# Dianome.net
KiCad netlist of a schematic drawn in EAGLE
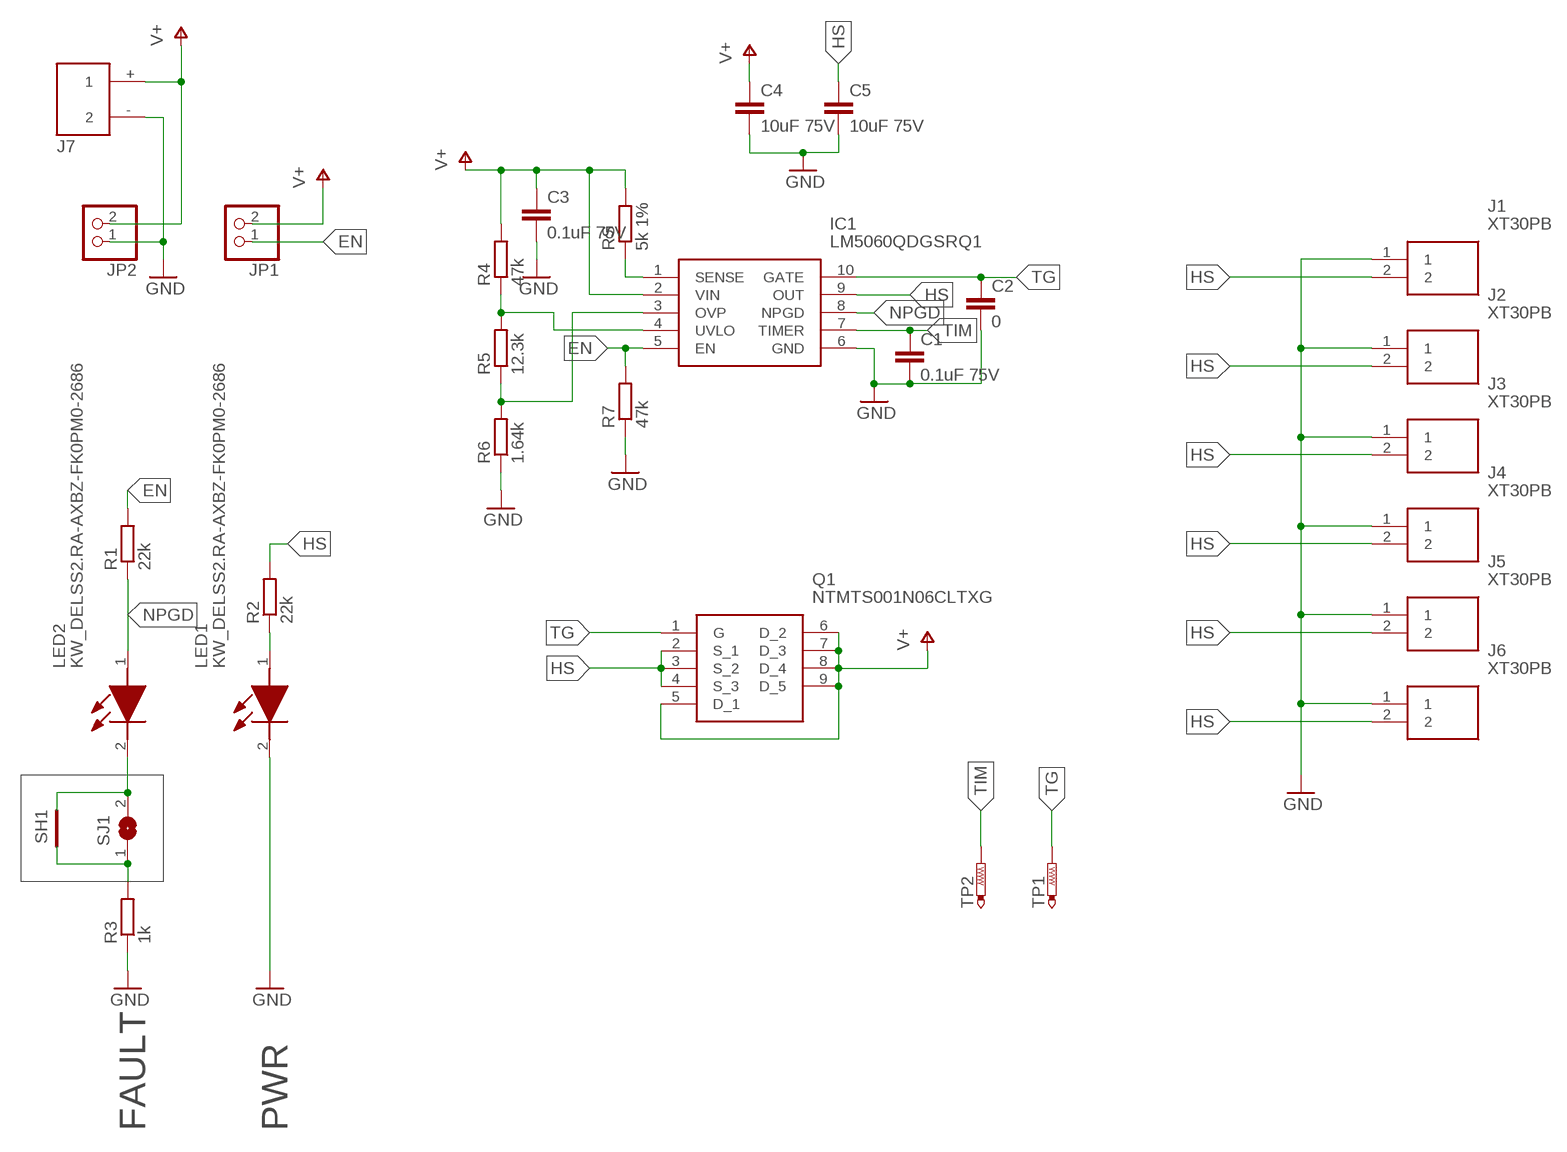
[diagram p0: schematic, sheet 1]

(export (version "E")
  (design (tool "Eeschema 10.0.6"))
  (components
    (comp (ref "C1")
      (value "0.1uF 75V")
      (footprint "eagle-import:C0603K")
      (libsource (lib "eagle-import") (part "C-EUC0603K"))
    )
    (comp (ref "C2")
      (value "0")
      (footprint "eagle-import:C0603K")
      (libsource (lib "eagle-import") (part "C-EUC0603K"))
    )
    (comp (ref "C3")
      (value "0.1uF 75V")
      (footprint "eagle-import:C0603K")
      (libsource (lib "eagle-import") (part "C-EUC0603K"))
    )
    (comp (ref "C4")
      (value "10uF 75V")
      (footprint "eagle-import:C1210")
      (libsource (lib "eagle-import") (part "C-EUC1210"))
    )
    (comp (ref "C5")
      (value "10uF 75V")
      (footprint "eagle-import:C1210")
      (libsource (lib "eagle-import") (part "C-EUC1210"))
    )
    (comp (ref "IC1")
      (value "LM5060QDGSRQ1")
      (footprint "eagle-import:SOP50P490X110-10N")
      (fields (field (name "MOUSER_PART_NUMBER") "595-LM5060QDGSRQ1"))
      (libsource (lib "eagle-import") (part "LM5060QDGSRQ1"))
    )
    (comp (ref "J1")
      (value "XT30PB")
      (footprint "eagle-import:XT30PB")
      (libsource (lib "eagle-import") (part "XT30PB"))
    )
    (comp (ref "J2")
      (value "XT30PB")
      (footprint "eagle-import:XT30PB")
      (libsource (lib "eagle-import") (part "XT30PB"))
    )
    (comp (ref "J3")
      (value "XT30PB")
      (footprint "eagle-import:XT30PB")
      (libsource (lib "eagle-import") (part "XT30PB"))
    )
    (comp (ref "J4")
      (value "XT30PB")
      (footprint "eagle-import:XT30PB")
      (libsource (lib "eagle-import") (part "XT30PB"))
    )
    (comp (ref "J5")
      (value "XT30PB")
      (footprint "eagle-import:XT30PB")
      (libsource (lib "eagle-import") (part "XT30PB"))
    )
    (comp (ref "J6")
      (value "XT30PB")
      (footprint "eagle-import:XT30PB")
      (libsource (lib "eagle-import") (part "XT30PB"))
    )
    (comp (ref "J7")
      (value "XT60_FEMALE")
      (footprint "eagle-import:XT60_FEMALE")
      (libsource (lib "eagle-import") (part "XT60_FEMALE"))
    )
    (comp (ref "JP1")
      (value "PINHD-1X02_2.54-S")
      (footprint "eagle-import:1X02-S")
      (libsource (lib "eagle-import") (part "PINHD-1X02_2.54-S"))
    )
    (comp (ref "JP2")
      (value "PINHD-1X02_2.54-S")
      (footprint "eagle-import:1X02-S")
      (libsource (lib "eagle-import") (part "PINHD-1X02_2.54-S"))
    )
    (comp (ref "LED1")
      (value "KW_DELSS2.RA-AXBZ-FK0PM0-2686")
      (footprint "eagle-import:KWDELSS2RAAXBZFK0PM02686")
      (fields
        (field (name "ARROW_PART_NUMBER") "KW DELSS2.RA-AXBZ-FK0PM0-2686")
        (field (name "MOUSER_PART_NUMBER") "720-KWDELSS2RAA6162")
      )
      (libsource (lib "eagle-import") (part "KW_DELSS2.RA-AXBZ-FK0PM0-2686"))
    )
    (comp (ref "LED2")
      (value "KW_DELSS2.RA-AXBZ-FK0PM0-2686")
      (footprint "eagle-import:KWDELSS2RAAXBZFK0PM02686")
      (fields
        (field (name "ARROW_PART_NUMBER") "KW DELSS2.RA-AXBZ-FK0PM0-2686")
        (field (name "MOUSER_PART_NUMBER") "720-KWDELSS2RAA6162")
      )
      (libsource (lib "eagle-import") (part "KW_DELSS2.RA-AXBZ-FK0PM0-2686"))
    )
    (comp (ref "Q1")
      (value "NTMTS001N06CLTXG")
      (footprint "eagle-import:NTMTS001N06CLTXG")
      (fields (field (name "MOUSER_PART_NUMBER") "863-NTMTS001N06CLTXG"))
      (libsource (lib "eagle-import") (part "NTMTS001N06CLTXG"))
    )
    (comp (ref "R1")
      (value "22k")
      (footprint "eagle-import:R0603")
      (libsource (lib "eagle-import") (part "R-EU_R0603"))
    )
    (comp (ref "R2")
      (value "22k")
      (footprint "eagle-import:R0603")
      (libsource (lib "eagle-import") (part "R-EU_R0603"))
    )
    (comp (ref "R3")
      (value "1k")
      (footprint "eagle-import:R0603")
      (libsource (lib "eagle-import") (part "R-EU_R0603"))
    )
    (comp (ref "R4")
      (value "47k")
      (footprint "eagle-import:R0603")
      (libsource (lib "eagle-import") (part "R-EU_R0603"))
    )
    (comp (ref "R5")
      (value "12.3k")
      (footprint "eagle-import:R0603")
      (libsource (lib "eagle-import") (part "R-EU_R0603"))
    )
    (comp (ref "R6")
      (value "1.64k")
      (footprint "eagle-import:R0603")
      (libsource (lib "eagle-import") (part "R-EU_R0603"))
    )
    (comp (ref "R7")
      (value "47k")
      (footprint "eagle-import:R0603")
      (libsource (lib "eagle-import") (part "R-EU_R0603"))
    )
    (comp (ref "RS")
      (value "5k 1%")
      (footprint "eagle-import:R0603")
      (libsource (lib "eagle-import") (part "R-EU_R0603"))
    )
    (comp (ref "SH1")
      (value "SHORTT5")
      (footprint "eagle-import:SHORT_TOP-50")
      (libsource (lib "eagle-import") (part "SHORTT5"))
    )
    (comp (ref "SJ1") (value "SJ") (footprint "eagle-import:SJ") (libsource (lib "eagle-import") (part "SJ")))
    (comp (ref "TP1")
      (value "PTR1PAD1-13")
      (footprint "eagle-import:P1-13")
      (libsource (lib "eagle-import") (part "PTR1PAD1-13"))
    )
    (comp (ref "TP2")
      (value "PTR1PAD1-13")
      (footprint "eagle-import:P1-13")
      (libsource (lib "eagle-import") (part "PTR1PAD1-13"))
    )
  )
  (nets
    (net (code "1") (name "EN") (class "Default")
      (node (ref "IC1") (pin "5") (pinfunction "EN_5") (pintype "bidirectional"))
      (node (ref "JP1") (pin "1") (pinfunction "1_1") (pintype "passive"))
      (node (ref "R1") (pin "2") (pinfunction "2_2") (pintype "passive"))
      (node (ref "R7") (pin "2") (pinfunction "2_2") (pintype "passive"))
    )
    (net (code "2") (name "GND") (class "Default")
      (node (ref "C1") (pin "2") (pinfunction "2_2") (pintype "passive"))
      (node (ref "C2") (pin "2") (pinfunction "2_2") (pintype "passive"))
      (node (ref "C3") (pin "2") (pinfunction "2_2") (pintype "passive"))
      (node (ref "C4") (pin "2") (pinfunction "2_2") (pintype "passive"))
      (node (ref "C5") (pin "2") (pinfunction "2_2") (pintype "passive"))
      (node (ref "IC1") (pin "6") (pinfunction "GND_6") (pintype "bidirectional"))
      (node (ref "J1") (pin "1") (pinfunction "1_1") (pintype "bidirectional"))
      (node (ref "J2") (pin "1") (pinfunction "1_1") (pintype "bidirectional"))
      (node (ref "J3") (pin "1") (pinfunction "1_1") (pintype "bidirectional"))
      (node (ref "J4") (pin "1") (pinfunction "1_1") (pintype "bidirectional"))
      (node (ref "J5") (pin "1") (pinfunction "1_1") (pintype "bidirectional"))
      (node (ref "J6") (pin "1") (pinfunction "1_1") (pintype "bidirectional"))
      (node (ref "J7") (pin "-") (pinfunction "2_-") (pintype "bidirectional"))
      (node (ref "JP2") (pin "1") (pinfunction "1_1") (pintype "passive"))
      (node (ref "LED1") (pin "2") (pinfunction "K_2") (pintype "bidirectional"))
      (node (ref "R3") (pin "1") (pinfunction "1_1") (pintype "passive"))
      (node (ref "R6") (pin "1") (pinfunction "1_1") (pintype "passive"))
      (node (ref "R7") (pin "1") (pinfunction "1_1") (pintype "passive"))
    )
    (net (code "3") (name "HS") (class "Default")
      (node (ref "C5") (pin "1") (pinfunction "1_1") (pintype "passive"))
      (node (ref "IC1") (pin "9") (pinfunction "OUT_9") (pintype "bidirectional"))
      (node (ref "J1") (pin "2") (pinfunction "2_2") (pintype "bidirectional"))
      (node (ref "J2") (pin "2") (pinfunction "2_2") (pintype "bidirectional"))
      (node (ref "J3") (pin "2") (pinfunction "2_2") (pintype "bidirectional"))
      (node (ref "J4") (pin "2") (pinfunction "2_2") (pintype "bidirectional"))
      (node (ref "J5") (pin "2") (pinfunction "2_2") (pintype "bidirectional"))
      (node (ref "J6") (pin "2") (pinfunction "2_2") (pintype "bidirectional"))
      (node (ref "Q1") (pin "2") (pinfunction "S_1_2") (pintype "bidirectional"))
      (node (ref "Q1") (pin "3") (pinfunction "S_2_3") (pintype "bidirectional"))
      (node (ref "Q1") (pin "4") (pinfunction "S_3_4") (pintype "bidirectional"))
      (node (ref "R2") (pin "2") (pinfunction "2_2") (pintype "passive"))
    )
    (net (code "4") (name "NPGD") (class "Default")
      (node (ref "IC1") (pin "8") (pinfunction "NPGD_8") (pintype "bidirectional"))
      (node (ref "LED2") (pin "1") (pinfunction "A_1") (pintype "bidirectional"))
      (node (ref "R1") (pin "1") (pinfunction "1_1") (pintype "passive"))
    )
    (net (code "5") (name "Net-(IC1-OVP)") (class "Default")
      (node (ref "IC1") (pin "3") (pinfunction "OVP_3") (pintype "bidirectional"))
      (node (ref "R5") (pin "1") (pinfunction "1_1") (pintype "passive"))
      (node (ref "R6") (pin "2") (pinfunction "2_2") (pintype "passive"))
    )
    (net (code "6") (name "Net-(IC1-SENSE)") (class "Default")
      (node (ref "IC1") (pin "1") (pinfunction "SENSE_1") (pintype "bidirectional"))
      (node (ref "RS") (pin "1") (pinfunction "1_1") (pintype "passive"))
    )
    (net (code "7") (name "Net-(IC1-UVLO)") (class "Default")
      (node (ref "IC1") (pin "4") (pinfunction "UVLO_4") (pintype "bidirectional"))
      (node (ref "R4") (pin "1") (pinfunction "1_1") (pintype "passive"))
      (node (ref "R5") (pin "2") (pinfunction "2_2") (pintype "passive"))
    )
    (net (code "8") (name "Net-(LED1-A)") (class "Default")
      (node (ref "LED1") (pin "1") (pinfunction "A_1") (pintype "bidirectional"))
      (node (ref "R2") (pin "1") (pinfunction "1_1") (pintype "passive"))
    )
    (net (code "9") (name "Net-(LED2-K)") (class "Default")
      (node (ref "LED2") (pin "2") (pinfunction "K_2") (pintype "bidirectional"))
      (node (ref "SH1") (pin "2") (pinfunction "P$2_2") (pintype "bidirectional"))
      (node (ref "SJ1") (pin "2") (pinfunction "2_2") (pintype "passive"))
    )
    (net (code "10") (name "Net-(SH1-P$1)") (class "Default")
      (node (ref "R3") (pin "2") (pinfunction "2_2") (pintype "passive"))
      (node (ref "SH1") (pin "1") (pinfunction "P$1_1") (pintype "bidirectional"))
      (node (ref "SJ1") (pin "1") (pinfunction "1_1") (pintype "passive"))
    )
    (net (code "11") (name "TG") (class "Default")
      (node (ref "C2") (pin "1") (pinfunction "1_1") (pintype "passive"))
      (node (ref "IC1") (pin "10") (pinfunction "GATE_10") (pintype "bidirectional"))
      (node (ref "Q1") (pin "1") (pinfunction "G_1") (pintype "bidirectional"))
      (node (ref "TP1") (pin "1") (pinfunction "TP_1") (pintype "input"))
    )
    (net (code "12") (name "TIM") (class "Default")
      (node (ref "C1") (pin "1") (pinfunction "1_1") (pintype "passive"))
      (node (ref "IC1") (pin "7") (pinfunction "TIMER_7") (pintype "bidirectional"))
      (node (ref "TP2") (pin "1") (pinfunction "TP_1") (pintype "input"))
    )
    (net (code "13") (name "V+") (class "Default")
      (node (ref "C3") (pin "1") (pinfunction "1_1") (pintype "passive"))
      (node (ref "C4") (pin "1") (pinfunction "1_1") (pintype "passive"))
      (node (ref "IC1") (pin "2") (pinfunction "VIN_2") (pintype "bidirectional"))
      (node (ref "J7") (pin "+") (pinfunction "1_+") (pintype "bidirectional"))
      (node (ref "JP1") (pin "2") (pinfunction "2_2") (pintype "passive"))
      (node (ref "JP2") (pin "2") (pinfunction "2_2") (pintype "passive"))
      (node (ref "Q1") (pin "5") (pinfunction "D_1_5") (pintype "bidirectional"))
      (node (ref "Q1") (pin "6") (pinfunction "D_2_6") (pintype "bidirectional"))
      (node (ref "Q1") (pin "7") (pinfunction "D_3_7") (pintype "bidirectional"))
      (node (ref "Q1") (pin "8") (pinfunction "D_4_8") (pintype "bidirectional"))
      (node (ref "Q1") (pin "9") (pinfunction "D_5_9") (pintype "bidirectional"))
      (node (ref "R4") (pin "2") (pinfunction "2_2") (pintype "passive"))
      (node (ref "RS") (pin "2") (pinfunction "2_2") (pintype "passive"))
    )
  )
)
